# 04_-_USB_INTERFACE.net
KiCad netlist of a schematic drawn in Altium Designer
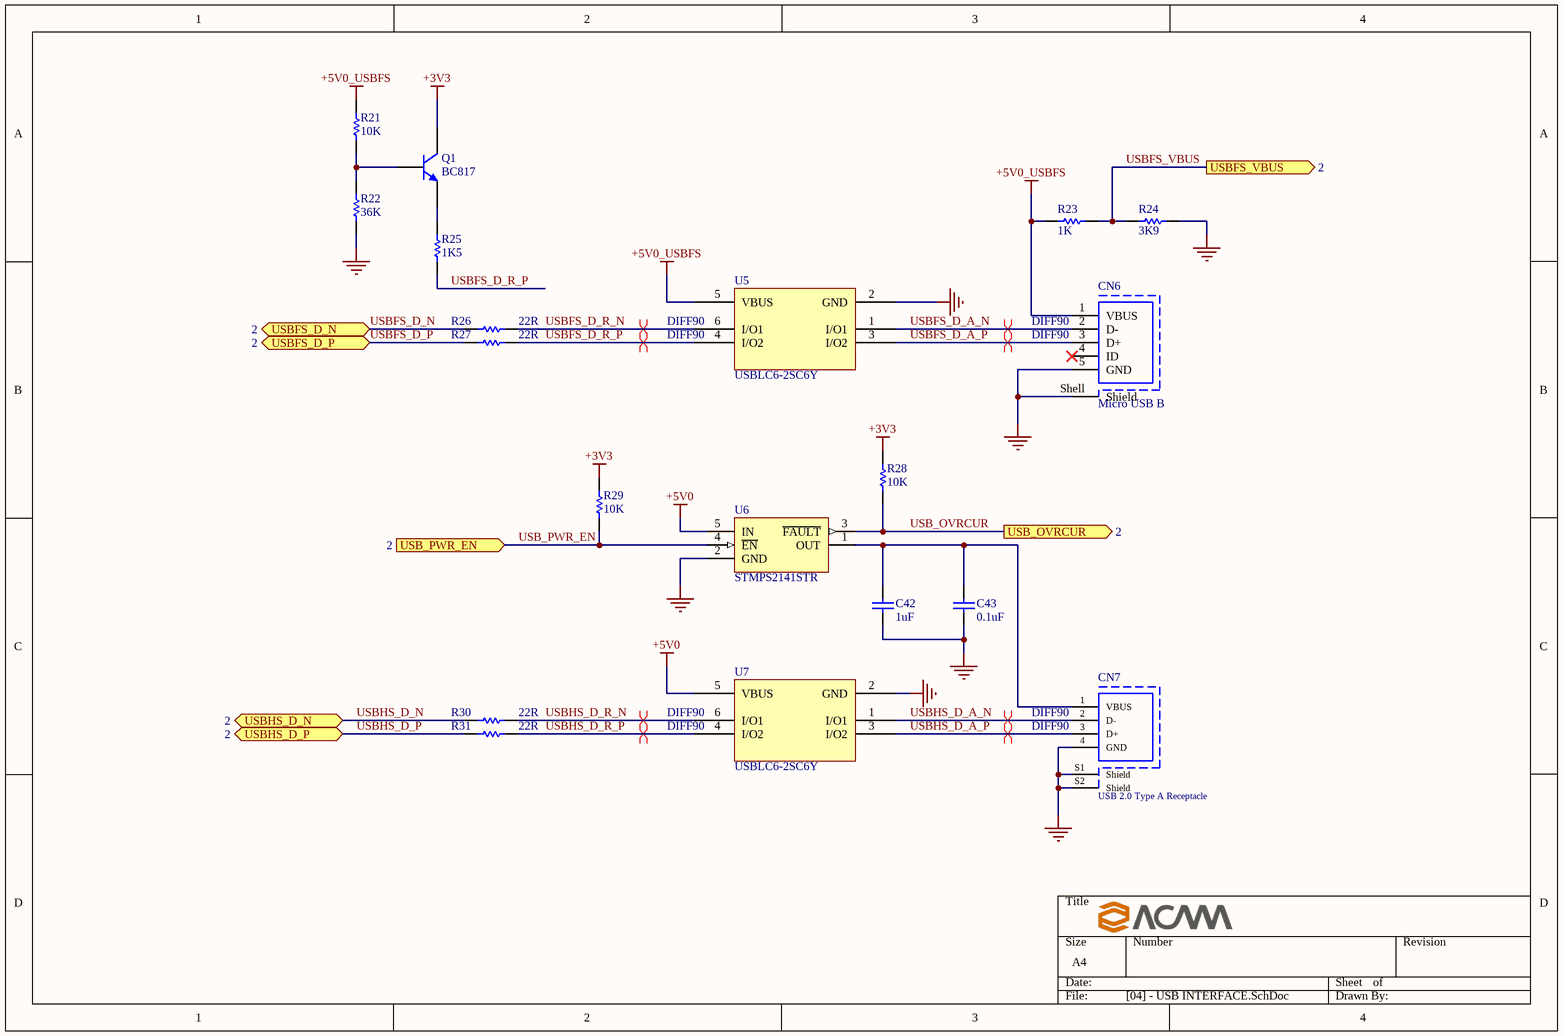
[diagram p0: [04] - USB INTERFACE.SchDoc]

(export (version "E")
  (design (tool "Eeschema 10.0.6"))
  (components
    (comp (ref "C42")
      (value "1uF")
      (footprint "0805_C_AUTO")
      (description "Non-Pol SMD Capacitor")
      (libsource (lib "Farzan Custom Library") (part "Cap SMD"))
    )
    (comp (ref "C43")
      (value "0.1uF")
      (footprint "0805_C_AUTO")
      (description "Non-Pol SMD Capacitor")
      (libsource (lib "Farzan Custom Library") (part "Cap SMD"))
    )
    (comp (ref "CN6")
      (value "Micro USB B")
      (footprint "USB_Micro_B")
      (description "Micro USB 2.0 Type B Receptacle")
      (libsource (lib "Farzan Custom Library") (part "USB Micro B #1"))
    )
    (comp (ref "CN7")
      (value "USB 2.0 Type A Receptacle")
      (footprint "USB_Type_A")
      (description "USB 2.0 Type A, Receptacle, Horizontal, THT")
      (libsource (lib "Farzan Custom Library") (part "USB Type A"))
    )
    (comp (ref "Q1")
      (value "BC817")
      (footprint "SOT23")
      (description "NPN General Purpose Transistor")
      (libsource (lib "Farzan Custom Library") (part "Transistor NPN"))
    )
    (comp (ref "R21")
      (value "10K")
      (footprint "0402_R")
      (description "SMD Resistor")
      (fields (field (name "TOLERANCE") "5%"))
      (libsource (lib "Farzan Custom Library") (part "Res SMD"))
    )
    (comp (ref "R22")
      (value "36K")
      (footprint "0402_R")
      (description "SMD Resistor")
      (fields (field (name "TOLERANCE") "5%"))
      (libsource (lib "Farzan Custom Library") (part "Res SMD"))
    )
    (comp (ref "R23")
      (value "1K")
      (footprint "0402_R")
      (description "SMD Resistor")
      (fields (field (name "TOLERANCE") "5%"))
      (libsource (lib "Farzan Custom Library") (part "Res SMD"))
    )
    (comp (ref "R24")
      (value "3K9")
      (footprint "0402_R")
      (description "SMD Resistor")
      (fields (field (name "TOLERANCE") "5%"))
      (libsource (lib "Farzan Custom Library") (part "Res SMD"))
    )
    (comp (ref "R25")
      (value "1K5")
      (footprint "0402_R")
      (description "SMD Resistor")
      (fields (field (name "TOLERANCE") "1%"))
      (libsource (lib "Farzan Custom Library") (part "Res SMD"))
    )
    (comp (ref "R26")
      (value "22R")
      (footprint "0402_R")
      (description "SMD Resistor")
      (fields (field (name "TOLERANCE") "5%"))
      (libsource (lib "Farzan Custom Library") (part "Res SMD"))
    )
    (comp (ref "R27")
      (value "22R")
      (footprint "0402_R")
      (description "SMD Resistor")
      (fields (field (name "TOLERANCE") "5%"))
      (libsource (lib "Farzan Custom Library") (part "Res SMD"))
    )
    (comp (ref "R28")
      (value "10K")
      (footprint "0402_R")
      (description "SMD Resistor")
      (fields (field (name "TOLERANCE") "5%"))
      (libsource (lib "Farzan Custom Library") (part "Res SMD"))
    )
    (comp (ref "R29")
      (value "10K")
      (footprint "0402_R")
      (description "SMD Resistor")
      (fields (field (name "TOLERANCE") "5%"))
      (libsource (lib "Farzan Custom Library") (part "Res SMD"))
    )
    (comp (ref "R30")
      (value "22R")
      (footprint "0402_R")
      (description "SMD Resistor")
      (fields (field (name "TOLERANCE") "5%"))
      (libsource (lib "Farzan Custom Library") (part "Res SMD"))
    )
    (comp (ref "R31")
      (value "22R")
      (footprint "0402_R")
      (description "SMD Resistor")
      (fields (field (name "TOLERANCE") "5%"))
      (libsource (lib "Farzan Custom Library") (part "Res SMD"))
    )
    (comp (ref "U5")
      (value "USBLC6-2SC6Y")
      (footprint "SOT23-6L")
      (description "Very low capacitance ESD protection")
      (libsource (lib "Farzan Custom Library") (part "USBLC6-2"))
    )
    (comp (ref "U6")
      (value "STMPS2141STR")
      (footprint "SOT-23-5pin")
      (libsource (lib "Farzan Custom Library") (part "STMPS2141"))
    )
    (comp (ref "U7")
      (value "USBLC6-2SC6Y")
      (footprint "SOT23-6L")
      (description "Very low capacitance ESD protection")
      (libsource (lib "Farzan Custom Library") (part "USBLC6-2"))
    )
  )
  (nets
    (net (code "1") (name "+3V3") (class "Default")
      (node (ref "Q1") (pin "3") (pinfunction "C_3") (pintype "passive"))
      (node (ref "R28") (pin "1") (pinfunction "1_1") (pintype "passive"))
      (node (ref "R29") (pin "1") (pinfunction "1_1") (pintype "passive"))
    )
    (net (code "2") (name "+5V0") (class "Default")
      (node (ref "U6") (pin "5") (pinfunction "IN_5") (pintype "power_in"))
      (node (ref "U7") (pin "5") (pinfunction "VBUS_5") (pintype "power_in"))
    )
    (net (code "3") (name "+5V0_USBFS") (class "Default")
      (node (ref "CN6") (pin "1") (pinfunction "VBUS_1") (pintype "passive"))
      (node (ref "R21") (pin "2") (pinfunction "2_2") (pintype "passive"))
      (node (ref "R23") (pin "2") (pinfunction "2_2") (pintype "passive"))
      (node (ref "U5") (pin "5") (pinfunction "VBUS_5") (pintype "power_in"))
    )
    (net (code "4") (name "/USBFS_D_A_N") (class "Default")
      (node (ref "CN6") (pin "2") (pinfunction "D-_2") (pintype "passive"))
      (node (ref "U5") (pin "1") (pinfunction "I/O1_1") (pintype "passive"))
    )
    (net (code "5") (name "/USBFS_D_A_P") (class "Default")
      (node (ref "CN6") (pin "3") (pinfunction "D+_3") (pintype "passive"))
      (node (ref "U5") (pin "3") (pinfunction "I/O2_3") (pintype "passive"))
    )
    (net (code "6") (name "/USBFS_D_N") (class "Default")
      (node (ref "R26") (pin "1") (pinfunction "1_1") (pintype "passive"))
    )
    (net (code "7") (name "/USBFS_D_P") (class "Default")
      (node (ref "R27") (pin "1") (pinfunction "1_1") (pintype "passive"))
    )
    (net (code "8") (name "/USBFS_D_R_N") (class "Default")
      (node (ref "R26") (pin "2") (pinfunction "2_2") (pintype "passive"))
      (node (ref "U5") (pin "6") (pinfunction "I/O1_6") (pintype "passive"))
    )
    (net (code "9") (name "/USBFS_D_R_P") (class "Default")
      (node (ref "R25") (pin "1") (pinfunction "1_1") (pintype "passive"))
      (node (ref "R27") (pin "2") (pinfunction "2_2") (pintype "passive"))
      (node (ref "U5") (pin "4") (pinfunction "I/O2_4") (pintype "passive"))
    )
    (net (code "10") (name "/USBFS_VBUS") (class "Default")
      (node (ref "R23") (pin "1") (pinfunction "1_1") (pintype "passive"))
      (node (ref "R24") (pin "2") (pinfunction "2_2") (pintype "passive"))
    )
    (net (code "11") (name "/USBHS_D_A_N") (class "Default")
      (node (ref "CN7") (pin "2") (pinfunction "D-_2") (pintype "passive"))
      (node (ref "U7") (pin "1") (pinfunction "I/O1_1") (pintype "passive"))
    )
    (net (code "12") (name "/USBHS_D_A_P") (class "Default")
      (node (ref "CN7") (pin "3") (pinfunction "D+_3") (pintype "passive"))
      (node (ref "U7") (pin "3") (pinfunction "I/O2_3") (pintype "passive"))
    )
    (net (code "13") (name "/USBHS_D_N") (class "Default")
      (node (ref "R30") (pin "1") (pinfunction "1_1") (pintype "passive"))
    )
    (net (code "14") (name "/USBHS_D_P") (class "Default")
      (node (ref "R31") (pin "1") (pinfunction "1_1") (pintype "passive"))
    )
    (net (code "15") (name "/USBHS_D_R_N") (class "Default")
      (node (ref "R30") (pin "2") (pinfunction "2_2") (pintype "passive"))
      (node (ref "U7") (pin "6") (pinfunction "I/O1_6") (pintype "passive"))
    )
    (net (code "16") (name "/USBHS_D_R_P") (class "Default")
      (node (ref "R31") (pin "2") (pinfunction "2_2") (pintype "passive"))
      (node (ref "U7") (pin "4") (pinfunction "I/O2_4") (pintype "passive"))
    )
    (net (code "17") (name "/USB_OVRCUR") (class "Default")
      (node (ref "R28") (pin "2") (pinfunction "2_2") (pintype "passive"))
      (node (ref "U6") (pin "3") (pinfunction "~{FAULT}_3") (pintype "output"))
    )
    (net (code "18") (name "/USB_PWR_EN") (class "Default")
      (node (ref "R29") (pin "2") (pinfunction "2_2") (pintype "passive"))
      (node (ref "U6") (pin "4") (pinfunction "~{EN}_4") (pintype "input"))
    )
    (net (code "19") (name "GND") (class "Default")
      (node (ref "C42") (pin "1") (pinfunction "1_1") (pintype "passive"))
      (node (ref "C43") (pin "1") (pinfunction "1_1") (pintype "passive"))
      (node (ref "CN6") (pin "5") (pinfunction "GND_5") (pintype "passive"))
      (node (ref "CN6") (pin "Shell") (pinfunction "Shield_Shell") (pintype "passive"))
      (node (ref "CN7") (pin "4") (pinfunction "GND_4") (pintype "passive"))
      (node (ref "CN7") (pin "S1") (pinfunction "Shield_S1") (pintype "passive"))
      (node (ref "CN7") (pin "S2") (pinfunction "Shield_S2") (pintype "passive"))
      (node (ref "R22") (pin "1") (pinfunction "1_1") (pintype "passive"))
      (node (ref "R24") (pin "1") (pinfunction "1_1") (pintype "passive"))
      (node (ref "U5") (pin "2") (pinfunction "GND_2") (pintype "power_in"))
      (node (ref "U6") (pin "2") (pinfunction "GND_2") (pintype "power_in"))
      (node (ref "U7") (pin "2") (pinfunction "GND_2") (pintype "power_in"))
    )
    (net (code "20") (name "Net-(CN7-VBUS)") (class "Default")
      (node (ref "C42") (pin "2") (pinfunction "2_2") (pintype "passive"))
      (node (ref "C43") (pin "2") (pinfunction "2_2") (pintype "passive"))
      (node (ref "CN7") (pin "1") (pinfunction "VBUS_1") (pintype "passive"))
      (node (ref "U6") (pin "1") (pinfunction "OUT_1") (pintype "power_in"))
    )
    (net (code "21") (name "Net-(Q1-B)") (class "Default")
      (node (ref "Q1") (pin "1") (pinfunction "B_1") (pintype "passive"))
      (node (ref "R21") (pin "1") (pinfunction "1_1") (pintype "passive"))
      (node (ref "R22") (pin "2") (pinfunction "2_2") (pintype "passive"))
    )
    (net (code "22") (name "Net-(Q1-E)") (class "Default")
      (node (ref "Q1") (pin "2") (pinfunction "E_2") (pintype "passive"))
      (node (ref "R25") (pin "2") (pinfunction "2_2") (pintype "passive"))
    )
    (net (code "23") (name "unconnected-(CN6-ID-Pad4)") (class "Default")
      (node (ref "CN6") (pin "4") (pinfunction "ID_4") (pintype "passive+no_connect"))
    )
  )
)
